# Candunio.net
KiCad netlist of a schematic drawn in Altium Designer
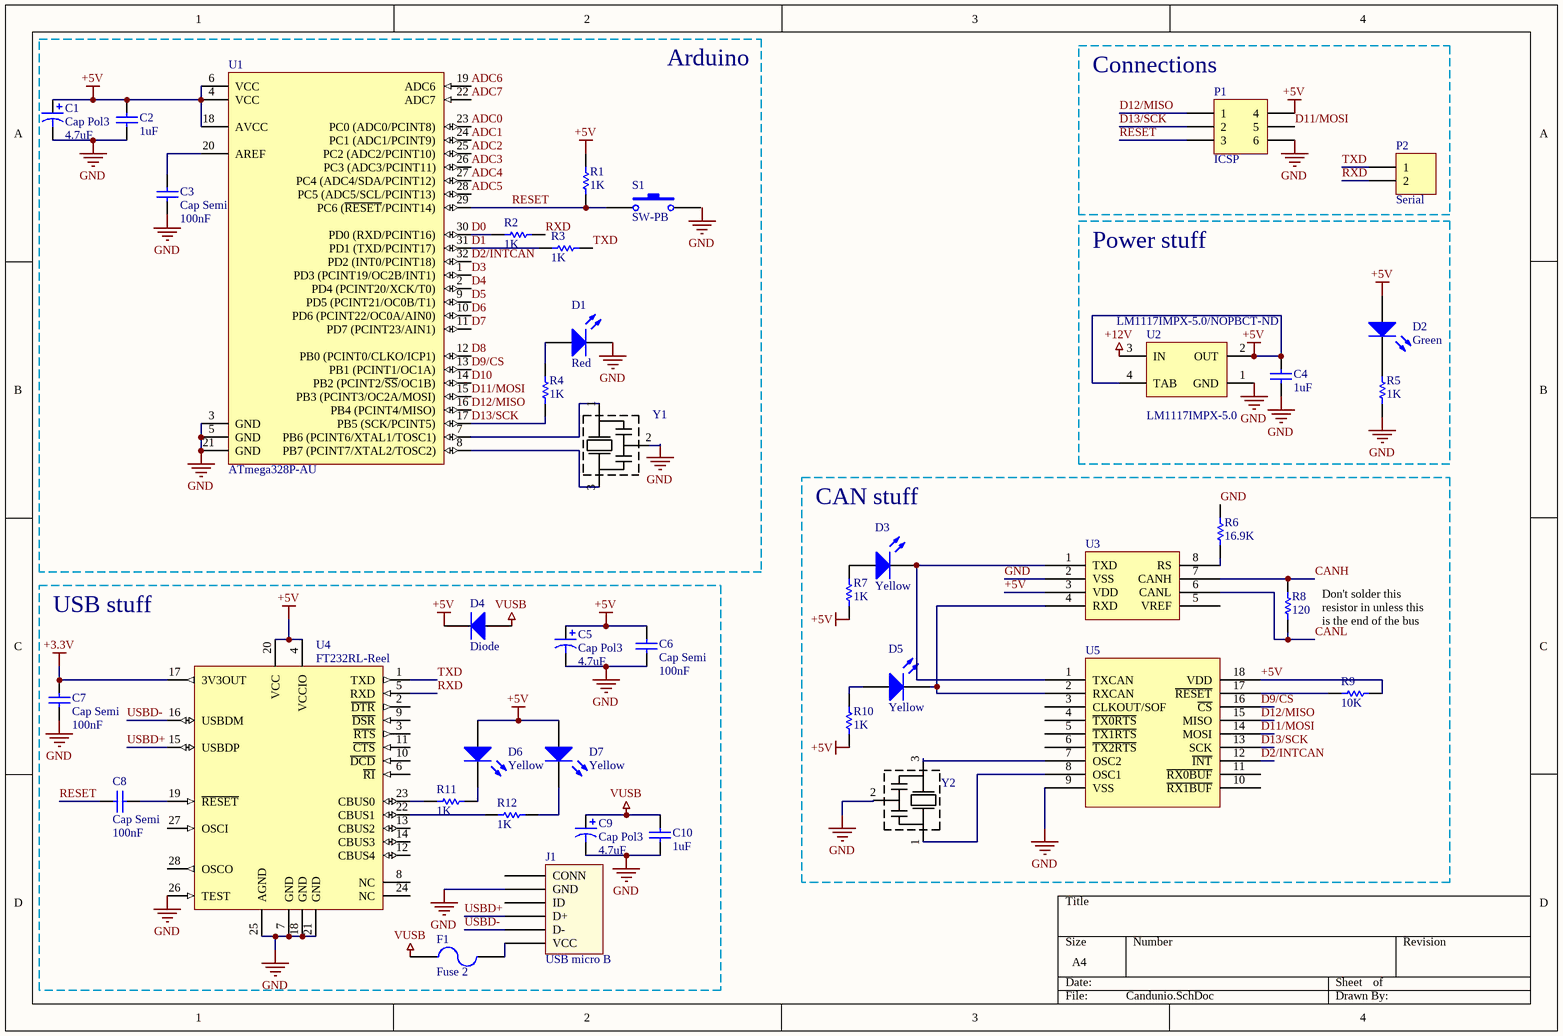
[diagram p0: Candunio.SchDoc]

(export (version "E")
  (design (tool "Eeschema 10.0.6"))
  (components
    (comp (ref "C1")
      (value "Cap Pol3")
      (footprint "C1206")
      (description "Polarized Capacitor (Surface Mount)")
      (fields
        (field (name "ALTIUM_VALUE") "4.7uF")
        (field (name "MANUFACTURER") "Kyocera AVX")
        (field (name "MANUFACTURER PART NUMBER") "12063C475KAT2A")
        (field (name "PUBLISHER") "Altium Limited")
      )
      (libsource (lib "Miscellaneous Devices") (part "Cap Pol3"))
    )
    (comp (ref "C2")
      (value "1uF")
      (footprint "C1206")
      (description "Capacitor (Semiconductor SIM Model)")
      (fields
        (field (name "MANUFACTURER") "Murata")
        (field (name "MANUFACTURER PART NUMBER") "GRM31MR71H105KA88L")
        (field (name "PUBLISHER") "Altium Limited")
      )
      (libsource (lib "Miscellaneous Devices") (part "Cap Semi"))
    )
    (comp (ref "C3")
      (value "Cap Semi")
      (footprint "C1206")
      (description "Capacitor (Semiconductor SIM Model)")
      (fields
        (field (name "ALTIUM_VALUE") "100nF")
        (field (name "MANUFACTURER") "Yageo")
        (field (name "MANUFACTURER PART NUMBER") "CC1206KKX7R0BB104")
        (field (name "PUBLISHER") "Altium Limited")
      )
      (libsource (lib "Miscellaneous Devices") (part "Cap Semi"))
    )
    (comp (ref "C4")
      (value "1uF")
      (footprint "C1206")
      (description "Capacitor (Semiconductor SIM Model)")
      (fields
        (field (name "MANUFACTURER") "Murata")
        (field (name "MANUFACTURER PART NUMBER") "GRM31MR71H105KA88L")
        (field (name "PUBLISHER") "Altium Limited")
      )
      (libsource (lib "Miscellaneous Devices") (part "Cap Semi"))
    )
    (comp (ref "C5")
      (value "Cap Pol3")
      (footprint "C1206")
      (description "Polarized Capacitor (Surface Mount)")
      (fields
        (field (name "ALTIUM_VALUE") "4.7uF")
        (field (name "MANUFACTURER") "Kyocera AVX")
        (field (name "MANUFACTURER PART NUMBER") "12063C475KAT2A")
        (field (name "PUBLISHER") "Altium Limited")
      )
      (libsource (lib "Miscellaneous Devices") (part "Cap Pol3"))
    )
    (comp (ref "C6")
      (value "Cap Semi")
      (footprint "C1206")
      (description "Capacitor (Semiconductor SIM Model)")
      (fields
        (field (name "ALTIUM_VALUE") "100nF")
        (field (name "MANUFACTURER") "Yageo")
        (field (name "MANUFACTURER PART NUMBER") "CC1206KKX7R0BB104")
        (field (name "PUBLISHER") "Altium Limited")
      )
      (libsource (lib "Miscellaneous Devices") (part "Cap Semi"))
    )
    (comp (ref "C7")
      (value "Cap Semi")
      (footprint "C1206")
      (description "Capacitor (Semiconductor SIM Model)")
      (fields
        (field (name "ALTIUM_VALUE") "100nF")
        (field (name "MANUFACTURER") "Yageo")
        (field (name "MANUFACTURER PART NUMBER") "CC1206KKX7R0BB104")
        (field (name "PUBLISHER") "Altium Limited")
      )
      (libsource (lib "Miscellaneous Devices") (part "Cap Semi"))
    )
    (comp (ref "C8")
      (value "Cap Semi")
      (footprint "C1206")
      (description "Capacitor (Semiconductor SIM Model)")
      (fields
        (field (name "ALTIUM_VALUE") "100nF")
        (field (name "MANUFACTURER") "Yageo")
        (field (name "MANUFACTURER PART NUMBER") "CC1206KKX7R0BB104")
        (field (name "PUBLISHER") "Altium Limited")
      )
      (libsource (lib "Miscellaneous Devices") (part "Cap Semi"))
    )
    (comp (ref "C9")
      (value "Cap Pol3")
      (footprint "C1206")
      (description "Polarized Capacitor (Surface Mount)")
      (fields
        (field (name "ALTIUM_VALUE") "4.7uF")
        (field (name "MANUFACTURER") "Kyocera AVX")
        (field (name "MANUFACTURER PART NUMBER") "12063C475KAT2A")
        (field (name "PUBLISHER") "Altium Limited")
      )
      (libsource (lib "Miscellaneous Devices") (part "Cap Pol3"))
    )
    (comp (ref "C10")
      (value "1uF")
      (footprint "C1206")
      (description "Capacitor (Semiconductor SIM Model)")
      (fields
        (field (name "MANUFACTURER") "Murata")
        (field (name "MANUFACTURER PART NUMBER") "GRM31MR71H105KA88L")
        (field (name "PUBLISHER") "Altium Limited")
      )
      (libsource (lib "Miscellaneous Devices") (part "Cap Semi"))
    )
    (comp (ref "D1")
      (value "Red")
      (footprint "3.2X1.6X1.1")
      (description "Typical RED, GREEN, YELLOW, AMBER GaAs LED")
      (fields
        (field (name "MANUFACTURER") "Broadcom Avago")
        (field (name "MANUFACTURER PART NUMBER") "HSMY-C150")
        (field (name "PUBLISHER") "Altium Limited")
      )
      (libsource (lib "Miscellaneous Devices") (part "LED2"))
    )
    (comp (ref "D2")
      (value "Green")
      (footprint "3.2X1.6X1.1")
      (description "Typical RED, GREEN, YELLOW, AMBER GaAs LED")
      (fields
        (field (name "MANUFACTURER") "Broadcom Avago")
        (field (name "MANUFACTURER PART NUMBER") "HSMG-C150")
        (field (name "PUBLISHER") "Altium Limited")
      )
      (libsource (lib "Miscellaneous Devices") (part "LED2"))
    )
    (comp (ref "D3")
      (value "Yellow")
      (footprint "3.2X1.6X1.1")
      (description "Typical RED, GREEN, YELLOW, AMBER GaAs LED")
      (fields
        (field (name "MANUFACTURER") "Broadcom Avago")
        (field (name "MANUFACTURER PART NUMBER") "HSMY-C150")
        (field (name "PUBLISHER") "Altium Limited")
      )
      (libsource (lib "Miscellaneous Devices") (part "LED2"))
    )
    (comp (ref "D4")
      (value "Diode")
      (footprint "SMC")
      (description "Default Diode")
      (fields (field (name "PUBLISHER") "Altium Limited"))
      (libsource (lib "Miscellaneous Devices") (part "Diode"))
    )
    (comp (ref "D5")
      (value "Yellow")
      (footprint "3.2X1.6X1.1")
      (description "Typical RED, GREEN, YELLOW, AMBER GaAs LED")
      (fields
        (field (name "MANUFACTURER") "Broadcom Avago")
        (field (name "MANUFACTURER PART NUMBER") "HSMY-C150")
        (field (name "PUBLISHER") "Altium Limited")
      )
      (libsource (lib "Miscellaneous Devices") (part "LED2"))
    )
    (comp (ref "D6")
      (value "Yellow")
      (footprint "3.2X1.6X1.1")
      (description "Typical RED, GREEN, YELLOW, AMBER GaAs LED")
      (fields
        (field (name "MANUFACTURER") "Broadcom Avago")
        (field (name "MANUFACTURER PART NUMBER") "HSMY-C150")
        (field (name "PUBLISHER") "Altium Limited")
      )
      (libsource (lib "Miscellaneous Devices") (part "LED2"))
    )
    (comp (ref "D7")
      (value "Yellow")
      (footprint "3.2X1.6X1.1")
      (description "Typical RED, GREEN, YELLOW, AMBER GaAs LED")
      (fields
        (field (name "MANUFACTURER") "Broadcom Avago")
        (field (name "MANUFACTURER PART NUMBER") "HSMY-C150")
        (field (name "PUBLISHER") "Altium Limited")
      )
      (libsource (lib "Miscellaneous Devices") (part "LED2"))
    )
    (comp (ref "F1")
      (value "Fuse 2")
      (footprint "1812")
      (description "Fuse")
      (fields
        (field (name "PART NUMBER") "MF-MSMF050-2")
        (field (name "MANUFACTURER") "Bourns")
        (field (name "PUBLISHER") "Altium Limited")
      )
      (libsource (lib "Miscellaneous Devices") (part "Fuse 2"))
    )
    (comp (ref "J1")
      (value "USB micro B")
      (footprint "1050170001")
      (description "CONN SM TH USB MICRO MODIFIED FOR DRILL")
      (fields (field (name "PART NUMBER") "WM1399CT-ND"))
      (libsource (lib "electronpowered") (part "1050170001"))
    )
    (comp (ref "P1")
      (value "ICSP")
      (footprint "HDR2X3_CEN")
      (description "Header, 3-Pin, Dual row")
      (fields (field (name "PUBLISHER") "Altium Limited"))
      (libsource (lib "Miscellaneous Connectors") (part "Header 3X2A"))
    )
    (comp (ref "P2")
      (value "Serial")
      (footprint "HDR1X2")
      (description "Header, 2-Pin")
      (fields (field (name "PUBLISHER") "Altium Limited"))
      (libsource (lib "Miscellaneous Connectors") (part "Header 2"))
    )
    (comp (ref "R1")
      (value "1K")
      (footprint "C1206")
      (description "Resistor")
      (fields
        (field (name "MANUFACTURER") "Stackpole Electronics")
        (field (name "MANUFACTURER PART NUMBER") "RNCP1206FTD1K00")
      )
      (libsource (lib "Miscellaneous Devices") (part "Res1"))
    )
    (comp (ref "R2")
      (value "1K")
      (footprint "C1206")
      (description "Resistor")
      (fields
        (field (name "MANUFACTURER") "Stackpole Electronics")
        (field (name "MANUFACTURER PART NUMBER") "RNCP1206FTD1K00")
      )
      (libsource (lib "Miscellaneous Devices") (part "Res1"))
    )
    (comp (ref "R3")
      (value "1K")
      (footprint "C1206")
      (description "Resistor")
      (fields
        (field (name "MANUFACTURER") "Stackpole Electronics")
        (field (name "MANUFACTURER PART NUMBER") "RNCP1206FTD1K00")
      )
      (libsource (lib "Miscellaneous Devices") (part "Res1"))
    )
    (comp (ref "R4")
      (value "1K")
      (footprint "C1206")
      (description "Resistor")
      (fields
        (field (name "MANUFACTURER") "Stackpole Electronics")
        (field (name "MANUFACTURER PART NUMBER") "RNCP1206FTD1K00")
      )
      (libsource (lib "Miscellaneous Devices") (part "Res1"))
    )
    (comp (ref "R5")
      (value "1K")
      (footprint "C1206")
      (description "Resistor")
      (fields
        (field (name "MANUFACTURER") "Stackpole Electronics")
        (field (name "MANUFACTURER PART NUMBER") "RNCP1206FTD1K00")
      )
      (libsource (lib "Miscellaneous Devices") (part "Res1"))
    )
    (comp (ref "R6")
      (value "16.9K")
      (footprint "C1206")
      (description "Resistor")
      (fields
        (field (name "MANUFACTURER") "TE Connectivity Holsworthy")
        (field (name "MANUFACTURER PART NUMBER") "CRGH1206F16K9")
      )
      (libsource (lib "Miscellaneous Devices") (part "Res1"))
    )
    (comp (ref "R7")
      (value "1K")
      (footprint "C1206")
      (description "Resistor")
      (fields
        (field (name "MANUFACTURER") "Stackpole Electronics")
        (field (name "MANUFACTURER PART NUMBER") "RNCP1206FTD1K00")
      )
      (libsource (lib "Miscellaneous Devices") (part "Res1"))
    )
    (comp (ref "R8")
      (value "120")
      (footprint "C1206")
      (description "Resistor")
      (fields
        (field (name "MANUFACTURER") "Vishay")
        (field (name "MANUFACTURER PART NUMBER") "CRCW1206120RFKEAHP")
      )
      (libsource (lib "Miscellaneous Devices") (part "Res1"))
    )
    (comp (ref "R9")
      (value "10K")
      (footprint "C1206")
      (description "Resistor")
      (fields
        (field (name "MANUFACTURER") "Stackpole Electronics")
        (field (name "MANUFACTURER PART NUMBER") "RNCP1206FTD10K0")
      )
      (libsource (lib "Miscellaneous Devices") (part "Res1"))
    )
    (comp (ref "R10")
      (value "1K")
      (footprint "C1206")
      (description "Resistor")
      (fields
        (field (name "MANUFACTURER") "Stackpole Electronics")
        (field (name "MANUFACTURER PART NUMBER") "RNCP1206FTD1K00")
      )
      (libsource (lib "Miscellaneous Devices") (part "Res1"))
    )
    (comp (ref "R11")
      (value "1K")
      (footprint "C1206")
      (description "Resistor")
      (fields
        (field (name "MANUFACTURER") "Stackpole Electronics")
        (field (name "MANUFACTURER PART NUMBER") "RNCP1206FTD1K00")
      )
      (libsource (lib "Miscellaneous Devices") (part "Res1"))
    )
    (comp (ref "R12")
      (value "1K")
      (footprint "C1206")
      (description "Resistor")
      (fields
        (field (name "MANUFACTURER") "Stackpole Electronics")
        (field (name "MANUFACTURER PART NUMBER") "RNCP1206FTD1K00")
      )
      (libsource (lib "Miscellaneous Devices") (part "Res1"))
    )
    (comp (ref "S1")
      (value "SW-PB")
      (footprint "C1206")
      (description "Switch")
      (fields
        (field (name "MANUFACTURER") "ITT C&K")
        (field (name "MANUFACTURER PART NUMBER") "KXT331LHS")
        (field (name "PUBLISHER") "Altium Limited")
      )
      (libsource (lib "Miscellaneous Devices") (part "SW-PB"))
    )
    (comp (ref "U1")
      (value "ATmega328P-AU")
      (footprint "32A_N")
      (fields (field (name "PUBLISHER") "Altium Limited"))
      (libsource (lib "Atmel Microcontroller 8-Bit megaAVR") (part "ATmega328P-AU"))
    )
    (comp (ref "U2")
      (value "LM1117IMPX-5.0")
      (footprint "MP04A_N")
      (description "800mA Low-Dropout Linear Regulator, 4-pin SOT-223")
      (fields
        (field (name "PARTNUMBER") "LM1117IMPX-5.0/NOPBCT-ND")
        (field (name "MANUFACTURER") "National Semiconductor")
        (field (name "SUPPLIER PART NUMBER") "LM1117IMPX-5.0/NOPBCT-ND")
        (field (name "PUBLISHER") "Altium Limited")
      )
      (libsource (lib "NSC LDO") (part "LM1117IMPX-5.0"))
    )
    (comp (ref "U3")
      (value "MCP2551-E/SN")
      (footprint "SOIC127P600X175-8M")
      (description "SOIC")
      (libsource (lib "AMSComponents") (part "MCP2551-E/SN"))
    )
    (comp (ref "U4")
      (value "FT232RL-Reel")
      (footprint "SSOP-28_N")
      (description "USB UART Asynchronous Serial Data Transfer Chip, SSOP-28, Tape and Reel")
      (fields
        (field (name "MANUFACTURER") "FTDI")
        (field (name "MANUFACTURER PART NUMBER") "FT232RL-REEL")
        (field (name "PUBLISHER") "Altium Limited")
      )
      (libsource (lib "FTDI Communication UART") (part "FT232RL-Reel"))
    )
    (comp (ref "U5")
      (value "MCP2515-E/ST")
      (footprint "SOIC127P1030X265-18M")
      (description "SOIC")
      (libsource (lib "AMSComponents") (part "MCP2515-E/ST"))
    )
    (comp (ref "Y1")
      (value "CSTCE16M0V53-R0")
      (footprint "CSTCE16M0V53-R0")
      (fields
        (field (name "MANUFACTURER") "Murata")
        (field (name "MANUFACTURER PART NUMBER") "CSTCE16M0V53C-R0")
        (field (name "TOLERANCE") "0.5%")
      )
      (libsource (lib "AMSComponents") (part "CSTCE16M0V53-R0"))
    )
    (comp (ref "Y2")
      (value "CSTCE16M0V53-R0")
      (footprint "CSTCE16M0V53-R0")
      (fields
        (field (name "MANUFACTURER") "Murata")
        (field (name "MANUFACTURER PART NUMBER") "CSTCE16M0V53C-R0")
        (field (name "TOLERANCE") "0.5%")
      )
      (libsource (lib "AMSComponents") (part "CSTCE16M0V53-R0"))
    )
  )
  (nets
    (net (code "1") (name "+3.3V") (class "Default")
      (node (ref "C7") (pin "1") (pinfunction "1_1") (pintype "passive"))
      (node (ref "U4") (pin "17") (pinfunction "3V3OUT_17") (pintype "output"))
    )
    (net (code "2") (name "+5V") (class "Default")
      (node (ref "C1") (pin "1") (pinfunction "1_1") (pintype "passive"))
      (node (ref "C2") (pin "1") (pinfunction "1_1") (pintype "passive"))
      (node (ref "C4") (pin "1") (pinfunction "1_1") (pintype "passive"))
      (node (ref "C5") (pin "1") (pinfunction "1_1") (pintype "passive"))
      (node (ref "C6") (pin "1") (pinfunction "1_1") (pintype "passive"))
      (node (ref "D2") (pin "1") (pinfunction "A_1") (pintype "passive"))
      (node (ref "D4") (pin "2") (pinfunction "K_2") (pintype "passive"))
      (node (ref "D6") (pin "1") (pinfunction "A_1") (pintype "passive"))
      (node (ref "D7") (pin "1") (pinfunction "A_1") (pintype "passive"))
      (node (ref "P1") (pin "4") (pinfunction "4_4") (pintype "passive"))
      (node (ref "R1") (pin "1") (pinfunction "1_1") (pintype "passive"))
      (node (ref "R10") (pin "2") (pinfunction "2_2") (pintype "passive"))
      (node (ref "R7") (pin "1") (pinfunction "1_1") (pintype "passive"))
      (node (ref "R9") (pin "2") (pinfunction "2_2") (pintype "passive"))
      (node (ref "U1") (pin "18") (pinfunction "AVCC_18") (pintype "power_in"))
      (node (ref "U1") (pin "4") (pinfunction "VCC_4") (pintype "power_in"))
      (node (ref "U1") (pin "6") (pinfunction "VCC_6") (pintype "power_in"))
      (node (ref "U2") (pin "2") (pinfunction "OUT_2") (pintype "power_in"))
      (node (ref "U2") (pin "4") (pinfunction "TAB_4") (pintype "power_in"))
      (node (ref "U3") (pin "3") (pinfunction "VDD_3") (pintype "passive"))
      (node (ref "U4") (pin "20") (pinfunction "VCC_20") (pintype "power_in"))
      (node (ref "U4") (pin "4") (pinfunction "VCCIO_4") (pintype "power_in"))
      (node (ref "U5") (pin "18") (pinfunction "VDD_18") (pintype "passive"))
    )
    (net (code "3") (name "+12V") (class "Default")
      (node (ref "U2") (pin "3") (pinfunction "IN_3") (pintype "power_in"))
    )
    (net (code "4") (name "/ADC0") (class "Default")
      (node (ref "U1") (pin "23") (pinfunction "PC0_(ADC0/PCINT8)_23") (pintype "bidirectional"))
    )
    (net (code "5") (name "/ADC1") (class "Default")
      (node (ref "U1") (pin "24") (pinfunction "PC1_(ADC1/PCINT9)_24") (pintype "bidirectional"))
    )
    (net (code "6") (name "/ADC2") (class "Default")
      (node (ref "U1") (pin "25") (pinfunction "PC2_(ADC2/PCINT10)_25") (pintype "bidirectional"))
    )
    (net (code "7") (name "/ADC3") (class "Default")
      (node (ref "U1") (pin "26") (pinfunction "PC3_(ADC3/PCINT11)_26") (pintype "bidirectional"))
    )
    (net (code "8") (name "/ADC4") (class "Default")
      (node (ref "U1") (pin "27") (pinfunction "PC4_(ADC4/SDA/PCINT12)_27") (pintype "bidirectional"))
    )
    (net (code "9") (name "/ADC5") (class "Default")
      (node (ref "U1") (pin "28") (pinfunction "PC5_(ADC5/SCL/PCINT13)_28") (pintype "bidirectional"))
    )
    (net (code "10") (name "/ADC6") (class "Default")
      (node (ref "U1") (pin "19") (pinfunction "ADC6_19") (pintype "input"))
    )
    (net (code "11") (name "/ADC7") (class "Default")
      (node (ref "U1") (pin "22") (pinfunction "ADC7_22") (pintype "input"))
    )
    (net (code "12") (name "/CANH") (class "Default")
      (node (ref "R8") (pin "1") (pinfunction "1_1") (pintype "passive"))
      (node (ref "U3") (pin "7") (pinfunction "CANH_7") (pintype "passive"))
    )
    (net (code "13") (name "/CANL") (class "Default")
      (node (ref "R8") (pin "2") (pinfunction "2_2") (pintype "passive"))
      (node (ref "U3") (pin "6") (pinfunction "CANL_6") (pintype "passive"))
    )
    (net (code "14") (name "/D0") (class "Default")
      (node (ref "R2") (pin "1") (pinfunction "1_1") (pintype "passive"))
      (node (ref "U1") (pin "30") (pinfunction "PD0_(RXD/PCINT16)_30") (pintype "bidirectional"))
    )
    (net (code "15") (name "/D1") (class "Default")
      (node (ref "R3") (pin "1") (pinfunction "1_1") (pintype "passive"))
      (node (ref "U1") (pin "31") (pinfunction "PD1_(TXD/PCINT17)_31") (pintype "bidirectional"))
    )
    (net (code "16") (name "/D2{slash}INTCAN") (class "Default")
      (node (ref "U1") (pin "32") (pinfunction "PD2_(INT0/PCINT18)_32") (pintype "bidirectional"))
      (node (ref "U5") (pin "12") (pinfunction "~{INT}_12") (pintype "passive"))
    )
    (net (code "17") (name "/D3") (class "Default")
      (node (ref "U1") (pin "1") (pinfunction "PD3_(PCINT19/OC2B/INT1)_1") (pintype "bidirectional"))
    )
    (net (code "18") (name "/D4") (class "Default")
      (node (ref "U1") (pin "2") (pinfunction "PD4_(PCINT20/XCK/T0)_2") (pintype "bidirectional"))
    )
    (net (code "19") (name "/D5") (class "Default")
      (node (ref "U1") (pin "9") (pinfunction "PD5_(PCINT21/OC0B/T1)_9") (pintype "bidirectional"))
    )
    (net (code "20") (name "/D6") (class "Default")
      (node (ref "U1") (pin "10") (pinfunction "PD6_(PCINT22/OC0A/AIN0)_10") (pintype "bidirectional"))
    )
    (net (code "21") (name "/D7") (class "Default")
      (node (ref "U1") (pin "11") (pinfunction "PD7_(PCINT23/AIN1)_11") (pintype "bidirectional"))
    )
    (net (code "22") (name "/D8") (class "Default")
      (node (ref "U1") (pin "12") (pinfunction "PB0_(PCINT0/CLKO/ICP1)_12") (pintype "bidirectional"))
    )
    (net (code "23") (name "/D9{slash}CS") (class "Default")
      (node (ref "U1") (pin "13") (pinfunction "PB1_(PCINT1/OC1A)_13") (pintype "bidirectional"))
      (node (ref "U5") (pin "16") (pinfunction "~{CS}_16") (pintype "passive"))
    )
    (net (code "24") (name "/D10") (class "Default")
      (node (ref "U1") (pin "14") (pinfunction "PB2_(PCINT2/~{SS}/OC1B)_14") (pintype "bidirectional"))
    )
    (net (code "25") (name "/D11{slash}MOSI") (class "Default")
      (node (ref "P1") (pin "5") (pinfunction "5_5") (pintype "passive"))
      (node (ref "U1") (pin "15") (pinfunction "PB3_(PCINT3/OC2A/MOSI)_15") (pintype "bidirectional"))
      (node (ref "U5") (pin "14") (pinfunction "MOSI_14") (pintype "passive"))
    )
    (net (code "26") (name "/D12{slash}MISO") (class "Default")
      (node (ref "P1") (pin "1") (pinfunction "1_1") (pintype "passive"))
      (node (ref "U1") (pin "16") (pinfunction "PB4_(PCINT4/MISO)_16") (pintype "bidirectional"))
      (node (ref "U5") (pin "15") (pinfunction "MISO_15") (pintype "passive"))
    )
    (net (code "27") (name "/D13{slash}SCK") (class "Default")
      (node (ref "P1") (pin "2") (pinfunction "2_2") (pintype "passive"))
      (node (ref "R4") (pin "2") (pinfunction "2_2") (pintype "passive"))
      (node (ref "U1") (pin "17") (pinfunction "PB5_(SCK/PCINT5)_17") (pintype "bidirectional"))
      (node (ref "U5") (pin "13") (pinfunction "SCK_13") (pintype "passive"))
    )
    (net (code "28") (name "/RESET") (class "Default")
      (node (ref "C8") (pin "1") (pinfunction "1_1") (pintype "passive"))
      (node (ref "P1") (pin "3") (pinfunction "3_3") (pintype "passive"))
      (node (ref "R1") (pin "2") (pinfunction "2_2") (pintype "passive"))
      (node (ref "S1") (pin "1") (pinfunction "1_1") (pintype "passive"))
      (node (ref "U1") (pin "29") (pinfunction "PC6_(~{RESET}/PCINT14)_29") (pintype "bidirectional"))
    )
    (net (code "29") (name "/RXD") (class "Default")
      (node (ref "P2") (pin "2") (pinfunction "2_2") (pintype "passive"))
      (node (ref "R2") (pin "2") (pinfunction "2_2") (pintype "passive"))
      (node (ref "U4") (pin "5") (pinfunction "RXD_5") (pintype "input"))
    )
    (net (code "30") (name "/TXD") (class "Default")
      (node (ref "P2") (pin "1") (pinfunction "1_1") (pintype "passive"))
      (node (ref "R3") (pin "2") (pinfunction "2_2") (pintype "passive"))
      (node (ref "U4") (pin "1") (pinfunction "TXD_1") (pintype "output"))
    )
    (net (code "31") (name "/USBD+") (class "Default")
      (node (ref "J1") (pin "3") (pinfunction "D+_3") (pintype "passive"))
      (node (ref "U4") (pin "15") (pinfunction "USBDP_15") (pintype "bidirectional"))
    )
    (net (code "32") (name "/USBD-") (class "Default")
      (node (ref "J1") (pin "2") (pinfunction "D-_2") (pintype "passive"))
      (node (ref "U4") (pin "16") (pinfunction "USBDM_16") (pintype "bidirectional"))
    )
    (net (code "33") (name "GND") (class "Default")
      (node (ref "C1") (pin "2") (pinfunction "2_2") (pintype "passive"))
      (node (ref "C10") (pin "2") (pinfunction "2_2") (pintype "passive"))
      (node (ref "C2") (pin "2") (pinfunction "2_2") (pintype "passive"))
      (node (ref "C3") (pin "2") (pinfunction "2_2") (pintype "passive"))
      (node (ref "C4") (pin "2") (pinfunction "2_2") (pintype "passive"))
      (node (ref "C5") (pin "2") (pinfunction "2_2") (pintype "passive"))
      (node (ref "C6") (pin "2") (pinfunction "2_2") (pintype "passive"))
      (node (ref "C7") (pin "2") (pinfunction "2_2") (pintype "passive"))
      (node (ref "C9") (pin "2") (pinfunction "2_2") (pintype "passive"))
      (node (ref "D1") (pin "2") (pinfunction "K_2") (pintype "passive"))
      (node (ref "J1") (pin "5") (pinfunction "GND_5") (pintype "passive"))
      (node (ref "P1") (pin "6") (pinfunction "6_6") (pintype "passive"))
      (node (ref "R5") (pin "2") (pinfunction "2_2") (pintype "passive"))
      (node (ref "R6") (pin "1") (pinfunction "1_1") (pintype "passive"))
      (node (ref "U1") (pin "21") (pinfunction "GND_21") (pintype "power_in"))
      (node (ref "U1") (pin "3") (pinfunction "GND_3") (pintype "power_in"))
      (node (ref "U1") (pin "5") (pinfunction "GND_5") (pintype "power_in"))
      (node (ref "U2") (pin "1") (pinfunction "GND_1") (pintype "power_in"))
      (node (ref "U3") (pin "2") (pinfunction "VSS_2") (pintype "passive"))
      (node (ref "U4") (pin "18") (pinfunction "GND_18") (pintype "power_in"))
      (node (ref "U4") (pin "21") (pinfunction "GND_21") (pintype "power_in"))
      (node (ref "U4") (pin "25") (pinfunction "AGND_25") (pintype "power_in"))
      (node (ref "U4") (pin "26") (pinfunction "TEST_26") (pintype "input"))
      (node (ref "U4") (pin "7") (pinfunction "GND_7") (pintype "power_in"))
      (node (ref "U5") (pin "9") (pinfunction "VSS_9") (pintype "passive"))
      (node (ref "Y1") (pin "2") (pinfunction "2_2") (pintype "passive"))
      (node (ref "Y2") (pin "2") (pinfunction "2_2") (pintype "passive"))
    )
    (net (code "34") (name "Net-(D1-A)") (class "Default")
      (node (ref "D1") (pin "1") (pinfunction "A_1") (pintype "passive"))
      (node (ref "R4") (pin "1") (pinfunction "1_1") (pintype "passive"))
    )
    (net (code "35") (name "Net-(D2-K)") (class "Default")
      (node (ref "D2") (pin "2") (pinfunction "K_2") (pintype "passive"))
      (node (ref "R5") (pin "1") (pinfunction "1_1") (pintype "passive"))
    )
    (net (code "36") (name "Net-(D3-A)") (class "Default")
      (node (ref "D3") (pin "1") (pinfunction "A_1") (pintype "passive"))
      (node (ref "R7") (pin "2") (pinfunction "2_2") (pintype "passive"))
    )
    (net (code "37") (name "Net-(D3-K)") (class "Default")
      (node (ref "D3") (pin "2") (pinfunction "K_2") (pintype "passive"))
      (node (ref "U3") (pin "1") (pinfunction "TXD_1") (pintype "passive"))
      (node (ref "U5") (pin "1") (pinfunction "TXCAN_1") (pintype "passive"))
    )
    (net (code "38") (name "Net-(D5-A)") (class "Default")
      (node (ref "D5") (pin "1") (pinfunction "A_1") (pintype "passive"))
      (node (ref "R10") (pin "1") (pinfunction "1_1") (pintype "passive"))
    )
    (net (code "39") (name "Net-(D5-K)") (class "Default")
      (node (ref "D5") (pin "2") (pinfunction "K_2") (pintype "passive"))
      (node (ref "U3") (pin "4") (pinfunction "RXD_4") (pintype "passive"))
      (node (ref "U5") (pin "2") (pinfunction "RXCAN_2") (pintype "passive"))
    )
    (net (code "40") (name "Net-(D6-K)") (class "Default")
      (node (ref "D6") (pin "2") (pinfunction "K_2") (pintype "passive"))
      (node (ref "R11") (pin "2") (pinfunction "2_2") (pintype "passive"))
    )
    (net (code "41") (name "Net-(D7-K)") (class "Default")
      (node (ref "D7") (pin "2") (pinfunction "K_2") (pintype "passive"))
      (node (ref "R12") (pin "2") (pinfunction "2_2") (pintype "passive"))
    )
    (net (code "42") (name "Net-(J1-VCC)") (class "Default")
      (node (ref "F1") (pin "2") (pinfunction "2_2") (pintype "passive"))
      (node (ref "J1") (pin "1") (pinfunction "VCC_1") (pintype "passive"))
    )
    (net (code "43") (name "Net-(U1-AREF)") (class "Default")
      (node (ref "C3") (pin "1") (pinfunction "1_1") (pintype "passive"))
      (node (ref "U1") (pin "20") (pinfunction "AREF_20") (pintype "passive"))
    )
    (net (code "44") (name "Net-(U1-PB6_(PCINT6{slash}XTAL1{slash}TOSC1))") (class "Default")
      (node (ref "U1") (pin "7") (pinfunction "PB6_(PCINT6/XTAL1/TOSC1)_7") (pintype "bidirectional"))
      (node (ref "Y1") (pin "1") (pinfunction "1_1") (pintype "passive"))
    )
    (net (code "45") (name "Net-(U1-PB7_(PCINT7{slash}XTAL2{slash}TOSC2))") (class "Default")
      (node (ref "U1") (pin "8") (pinfunction "PB7_(PCINT7/XTAL2/TOSC2)_8") (pintype "bidirectional"))
      (node (ref "Y1") (pin "3") (pinfunction "3_3") (pintype "passive"))
    )
    (net (code "46") (name "Net-(U3-RS)") (class "Default")
      (node (ref "R6") (pin "2") (pinfunction "2_2") (pintype "passive"))
      (node (ref "U3") (pin "8") (pinfunction "RS_8") (pintype "passive"))
    )
    (net (code "47") (name "Net-(U4-CBUS0)") (class "Default")
      (node (ref "R11") (pin "1") (pinfunction "1_1") (pintype "passive"))
      (node (ref "U4") (pin "23") (pinfunction "CBUS0_23") (pintype "bidirectional"))
    )
    (net (code "48") (name "Net-(U4-CBUS1)") (class "Default")
      (node (ref "R12") (pin "1") (pinfunction "1_1") (pintype "passive"))
      (node (ref "U4") (pin "22") (pinfunction "CBUS1_22") (pintype "bidirectional"))
    )
    (net (code "49") (name "Net-(U4-~{RESET})") (class "Default")
      (node (ref "C8") (pin "2") (pinfunction "2_2") (pintype "passive"))
      (node (ref "U4") (pin "19") (pinfunction "~{RESET}_19") (pintype "input"))
    )
    (net (code "50") (name "Net-(U5-OSC1)") (class "Default")
      (node (ref "U5") (pin "8") (pinfunction "OSC1_8") (pintype "passive"))
      (node (ref "Y2") (pin "1") (pinfunction "1_1") (pintype "passive"))
    )
    (net (code "51") (name "Net-(U5-OSC2)") (class "Default")
      (node (ref "U5") (pin "7") (pinfunction "OSC2_7") (pintype "passive"))
      (node (ref "Y2") (pin "3") (pinfunction "3_3") (pintype "passive"))
    )
    (net (code "52") (name "Net-(U5-~{RESET})") (class "Default")
      (node (ref "R9") (pin "1") (pinfunction "1_1") (pintype "passive"))
      (node (ref "U5") (pin "17") (pinfunction "~{RESET}_17") (pintype "passive"))
    )
    (net (code "53") (name "VUSB") (class "Default")
      (node (ref "C10") (pin "1") (pinfunction "1_1") (pintype "passive"))
      (node (ref "C9") (pin "1") (pinfunction "1_1") (pintype "passive"))
      (node (ref "D4") (pin "1") (pinfunction "A_1") (pintype "passive"))
      (node (ref "F1") (pin "1") (pinfunction "1_1") (pintype "passive"))
    )
    (net (code "54") (name "unconnected-(J1-CONN-Pad0)") (class "Default")
      (node (ref "J1") (pin "0") (pinfunction "CONN_0") (pintype "passive"))
    )
    (net (code "55") (name "unconnected-(J1-ID-Pad4)") (class "Default")
      (node (ref "J1") (pin "4") (pinfunction "ID_4") (pintype "passive"))
    )
    (net (code "56") (name "unconnected-(S1-Pad2)") (class "Default")
      (node (ref "S1") (pin "2") (pinfunction "2_2") (pintype "passive"))
    )
    (net (code "57") (name "unconnected-(U3-VREF-Pad5)") (class "Default")
      (node (ref "U3") (pin "5") (pinfunction "VREF_5") (pintype "passive"))
    )
    (net (code "58") (name "unconnected-(U4-CBUS2-Pad13)") (class "Default")
      (node (ref "U4") (pin "13") (pinfunction "CBUS2_13") (pintype "bidirectional"))
    )
    (net (code "59") (name "unconnected-(U4-CBUS3-Pad14)") (class "Default")
      (node (ref "U4") (pin "14") (pinfunction "CBUS3_14") (pintype "bidirectional"))
    )
    (net (code "60") (name "unconnected-(U4-CBUS4-Pad12)") (class "Default")
      (node (ref "U4") (pin "12") (pinfunction "CBUS4_12") (pintype "bidirectional"))
    )
    (net (code "61") (name "unconnected-(U4-NC-Pad8)") (class "Default")
      (node (ref "U4") (pin "8") (pinfunction "NC_8") (pintype "passive"))
    )
    (net (code "62") (name "unconnected-(U4-NC-Pad24)") (class "Default")
      (node (ref "U4") (pin "24") (pinfunction "NC_24") (pintype "passive"))
    )
    (net (code "63") (name "unconnected-(U4-OSCI-Pad27)") (class "Default")
      (node (ref "U4") (pin "27") (pinfunction "OSCI_27") (pintype "input"))
    )
    (net (code "64") (name "unconnected-(U4-OSCO-Pad28)") (class "Default")
      (node (ref "U4") (pin "28") (pinfunction "OSCO_28") (pintype "output"))
    )
    (net (code "65") (name "unconnected-(U4-~{CTS}-Pad11)") (class "Default")
      (node (ref "U4") (pin "11") (pinfunction "~{CTS}_11") (pintype "input"))
    )
    (net (code "66") (name "unconnected-(U4-~{DCD}-Pad10)") (class "Default")
      (node (ref "U4") (pin "10") (pinfunction "~{DCD}_10") (pintype "input"))
    )
    (net (code "67") (name "unconnected-(U4-~{DSR}-Pad9)") (class "Default")
      (node (ref "U4") (pin "9") (pinfunction "~{DSR}_9") (pintype "input"))
    )
    (net (code "68") (name "unconnected-(U4-~{DTR}-Pad2)") (class "Default")
      (node (ref "U4") (pin "2") (pinfunction "~{DTR}_2") (pintype "output"))
    )
    (net (code "69") (name "unconnected-(U4-~{RI}-Pad6)") (class "Default")
      (node (ref "U4") (pin "6") (pinfunction "~{RI}_6") (pintype "input"))
    )
    (net (code "70") (name "unconnected-(U4-~{RTS}-Pad3)") (class "Default")
      (node (ref "U4") (pin "3") (pinfunction "~{RTS}_3") (pintype "output"))
    )
    (net (code "71") (name "unconnected-(U5-CLKOUT{slash}SOF-Pad3)") (class "Default")
      (node (ref "U5") (pin "3") (pinfunction "CLKOUT/SOF_3") (pintype "passive"))
    )
    (net (code "72") (name "unconnected-(U5-~{RX0BUF}-Pad11)") (class "Default")
      (node (ref "U5") (pin "11") (pinfunction "~{RX0BUF}_11") (pintype "passive"))
    )
    (net (code "73") (name "unconnected-(U5-~{RX1BUF}-Pad10)") (class "Default")
      (node (ref "U5") (pin "10") (pinfunction "~{RX1BUF}_10") (pintype "passive"))
    )
    (net (code "74") (name "unconnected-(U5-~{TX0RTS}-Pad4)") (class "Default")
      (node (ref "U5") (pin "4") (pinfunction "~{TX0RTS}_4") (pintype "passive"))
    )
    (net (code "75") (name "unconnected-(U5-~{TX1RTS}-Pad5)") (class "Default")
      (node (ref "U5") (pin "5") (pinfunction "~{TX1RTS}_5") (pintype "passive"))
    )
    (net (code "76") (name "unconnected-(U5-~{TX2RTS}-Pad6)") (class "Default")
      (node (ref "U5") (pin "6") (pinfunction "~{TX2RTS}_6") (pintype "passive"))
    )
  )
)
